# BoomIMU_Sensor.net
KiCad netlist of a schematic drawn in Altium Designer
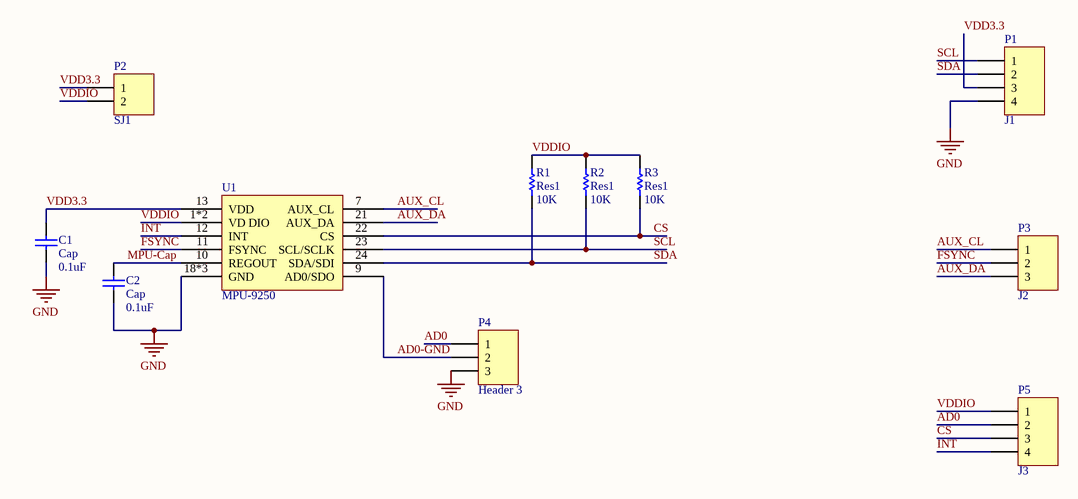
[diagram p0: BoomIMU_Sensor.SchDoc]

(export (version "E")
  (design (tool "Eeschema 10.0.6"))
  (components
    (comp (ref "C1")
      (value "Cap")
      (footprint "C1206")
      (description "Capacitor")
      (fields (field (name "ALTIUM_VALUE") "0.1uF") (field (name "PUBLISHER") "Altium Limited"))
      (libsource (lib "Miscellaneous Devices") (part "Cap"))
    )
    (comp (ref "C2")
      (value "Cap")
      (footprint "C1206")
      (description "Capacitor")
      (fields (field (name "ALTIUM_VALUE") "0.1uF") (field (name "PUBLISHER") "Altium Limited"))
      (libsource (lib "Miscellaneous Devices") (part "Cap"))
    )
    (comp (ref "P1")
      (value "J1")
      (footprint "HDR1X4")
      (description "Header, 4-Pin")
      (fields (field (name "PUBLISHER") "Altium Limited"))
      (libsource (lib "Miscellaneous Connectors") (part "Header 4"))
    )
    (comp (ref "P2")
      (value "SJ1")
      (footprint "HDR1X2")
      (description "Header, 2-Pin")
      (fields (field (name "PUBLISHER") "Altium Limited"))
      (libsource (lib "Miscellaneous Connectors") (part "Header 2"))
    )
    (comp (ref "P3")
      (value "J2")
      (footprint "HDR1X3")
      (description "Header, 3-Pin")
      (fields (field (name "PUBLISHER") "Altium Limited"))
      (libsource (lib "Miscellaneous Connectors") (part "Header 3"))
    )
    (comp (ref "P4")
      (value "Header 3")
      (footprint "HDR1X3")
      (description "Header, 3-Pin")
      (fields (field (name "PUBLISHER") "Altium Limited"))
      (libsource (lib "Miscellaneous Connectors") (part "Header 3"))
    )
    (comp (ref "P5")
      (value "J3")
      (footprint "HDR1X4")
      (description "Header, 4-Pin")
      (fields (field (name "PUBLISHER") "Altium Limited"))
      (libsource (lib "Miscellaneous Connectors") (part "Header 4"))
    )
    (comp (ref "R1")
      (value "Res1")
      (footprint "C1206")
      (description "Resistor")
      (fields (field (name "ALTIUM_VALUE") "10K") (field (name "PUBLISHER") "Altium Limited"))
      (libsource (lib "Miscellaneous Devices") (part "Res1"))
    )
    (comp (ref "R2")
      (value "Res1")
      (footprint "C1206")
      (description "Resistor")
      (fields (field (name "ALTIUM_VALUE") "10K") (field (name "PUBLISHER") "Altium Limited"))
      (libsource (lib "Miscellaneous Devices") (part "Res1"))
    )
    (comp (ref "R3")
      (value "Res1")
      (footprint "C1206")
      (description "Resistor")
      (fields (field (name "ALTIUM_VALUE") "10K") (field (name "PUBLISHER") "Altium Limited"))
      (libsource (lib "Miscellaneous Devices") (part "Res1"))
    )
    (comp (ref "U1") (value "MPU-9250") (footprint "MPU-9250") (libsource (lib "MPU-9250") (part "MPU-9250")))
  )
  (nets
    (net (code "1") (name "/AD0") (class "Default")
      (node (ref "P4") (pin "1") (pinfunction "1_1") (pintype "passive"))
      (node (ref "P5") (pin "2") (pinfunction "2_2") (pintype "passive"))
    )
    (net (code "2") (name "/AD0-GND") (class "Default")
      (node (ref "P4") (pin "2") (pinfunction "2_2") (pintype "passive"))
      (node (ref "U1") (pin "9") (pinfunction "AD0/SDO_9") (pintype "passive"))
    )
    (net (code "3") (name "/AUX_CL") (class "Default")
      (node (ref "P3") (pin "1") (pinfunction "1_1") (pintype "passive"))
      (node (ref "U1") (pin "7") (pinfunction "AUX_CL_7") (pintype "passive"))
    )
    (net (code "4") (name "/AUX_DA") (class "Default")
      (node (ref "P3") (pin "3") (pinfunction "3_3") (pintype "passive"))
      (node (ref "U1") (pin "21") (pinfunction "AUX_DA_21") (pintype "passive"))
    )
    (net (code "5") (name "/CS") (class "Default")
      (node (ref "P5") (pin "3") (pinfunction "3_3") (pintype "passive"))
      (node (ref "R3") (pin "1") (pinfunction "1_1") (pintype "passive"))
      (node (ref "U1") (pin "22") (pinfunction "CS_22") (pintype "passive"))
    )
    (net (code "6") (name "/FSYNC") (class "Default")
      (node (ref "P3") (pin "2") (pinfunction "2_2") (pintype "passive"))
      (node (ref "U1") (pin "11") (pinfunction "FSYNC_11") (pintype "passive"))
    )
    (net (code "7") (name "/INT") (class "Default")
      (node (ref "P5") (pin "4") (pinfunction "4_4") (pintype "passive"))
      (node (ref "U1") (pin "12") (pinfunction "INT_12") (pintype "passive"))
    )
    (net (code "8") (name "/MPU-Cap") (class "Default")
      (node (ref "C2") (pin "2") (pinfunction "2_2") (pintype "passive"))
      (node (ref "U1") (pin "10") (pinfunction "REGOUT_10") (pintype "passive"))
    )
    (net (code "9") (name "/SCL") (class "Default")
      (node (ref "P1") (pin "1") (pinfunction "1_1") (pintype "passive"))
      (node (ref "R2") (pin "1") (pinfunction "1_1") (pintype "passive"))
      (node (ref "U1") (pin "23") (pinfunction "SCL/SCLK_23") (pintype "passive"))
    )
    (net (code "10") (name "/SDA") (class "Default")
      (node (ref "P1") (pin "2") (pinfunction "2_2") (pintype "passive"))
      (node (ref "R1") (pin "1") (pinfunction "1_1") (pintype "passive"))
      (node (ref "U1") (pin "24") (pinfunction "SDA/SDI_24") (pintype "passive"))
    )
    (net (code "11") (name "/VDD3.3") (class "Default")
      (node (ref "C1") (pin "2") (pinfunction "2_2") (pintype "passive"))
      (node (ref "P1") (pin "3") (pinfunction "3_3") (pintype "passive"))
      (node (ref "P2") (pin "1") (pinfunction "1_1") (pintype "passive"))
      (node (ref "U1") (pin "13") (pinfunction "VDD_13") (pintype "passive"))
    )
    (net (code "12") (name "/VDDIO") (class "Default")
      (node (ref "P2") (pin "2") (pinfunction "2_2") (pintype "passive"))
      (node (ref "P5") (pin "1") (pinfunction "1_1") (pintype "passive"))
      (node (ref "R1") (pin "2") (pinfunction "2_2") (pintype "passive"))
      (node (ref "R2") (pin "2") (pinfunction "2_2") (pintype "passive"))
      (node (ref "R3") (pin "2") (pinfunction "2_2") (pintype "passive"))
      (node (ref "U1") (pin "1*2") (pinfunction "VD_DIO_1*2") (pintype "passive"))
    )
    (net (code "13") (name "GND") (class "Default")
      (node (ref "C1") (pin "1") (pinfunction "1_1") (pintype "passive"))
      (node (ref "C2") (pin "1") (pinfunction "1_1") (pintype "passive"))
      (node (ref "P1") (pin "4") (pinfunction "4_4") (pintype "passive"))
      (node (ref "P4") (pin "3") (pinfunction "3_3") (pintype "passive"))
      (node (ref "U1") (pin "18*3") (pinfunction "GND_18*3") (pintype "passive"))
    )
  )
)
